# Audio_Output.net
KiCad netlist of a schematic drawn in Altium Designer
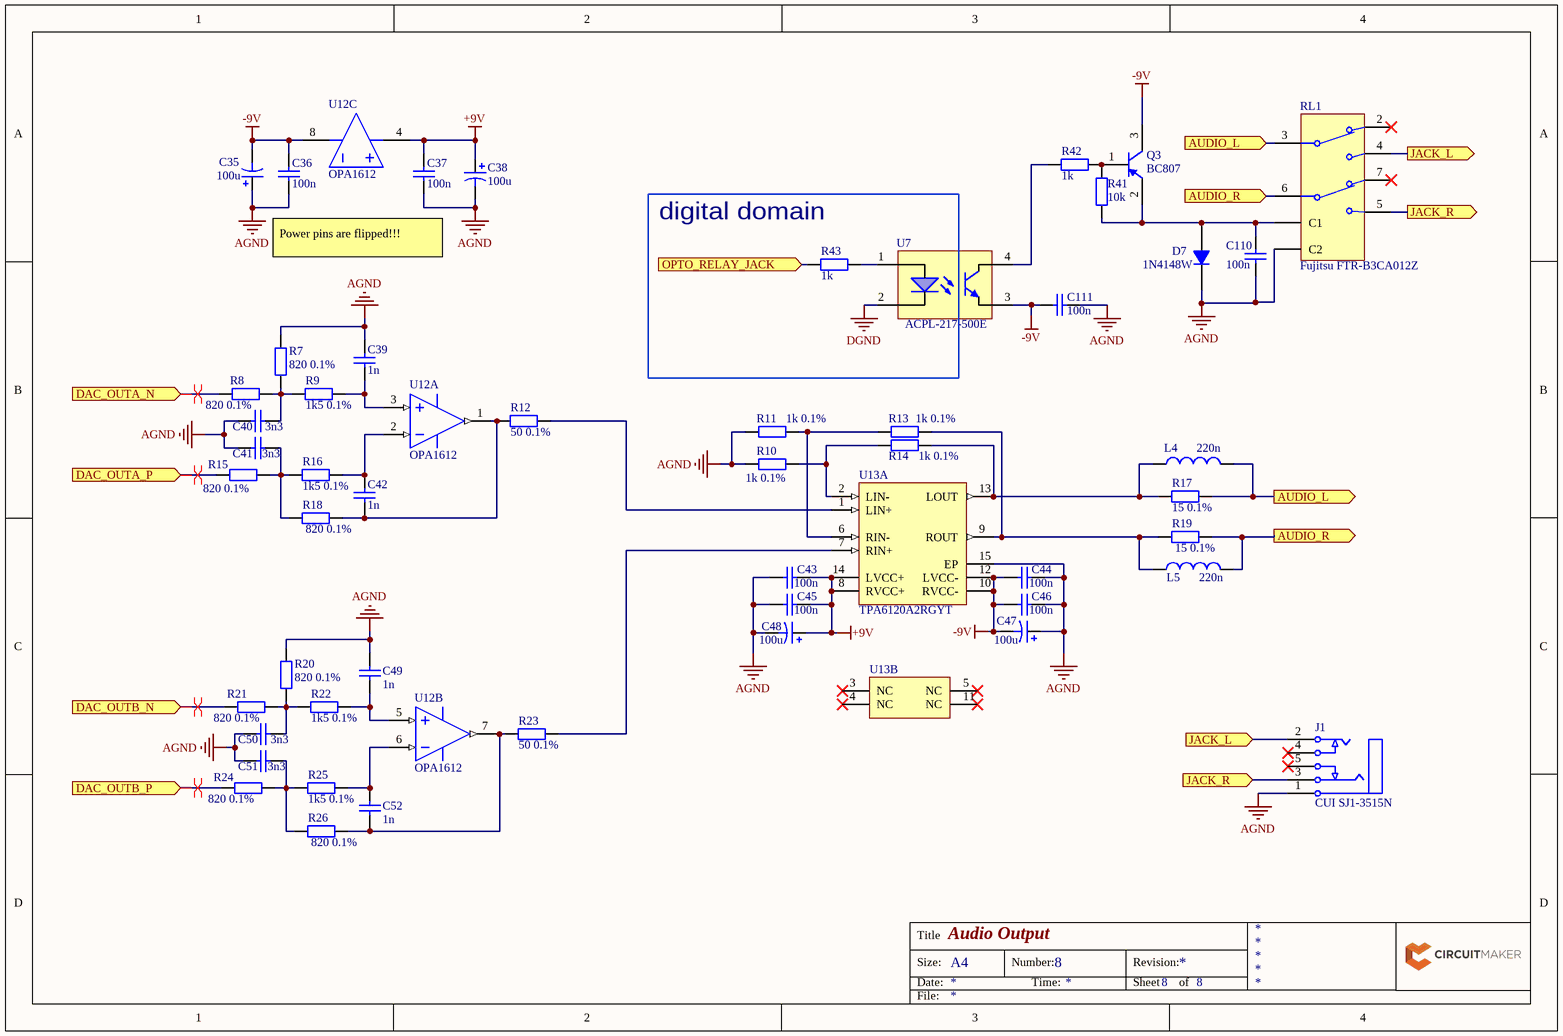
[diagram p0: Audio_Output.SchDoc]

(export (version "E")
  (design (tool "Eeschema 10.0.6"))
  (components
    (comp (ref "C35")
      (value "100u")
      (footprint "PCB-9bfrndi9huxo1n7cihpl-1")
      (description "In a Pack of 25, KEMET 100?F Electrolytic Capacitor 10V dc Through Hole - A758EK107M1AAAE016")
      (fields (field (name "MANUFACTURER PART NUMBER") "A758EK107M1AAAE016"))
      (libsource (lib "FavoritesLibrary") (part "SYM-6546a831a81eba81-3"))
    )
    (comp (ref "C36")
      (value "100n")
      (footprint "PCB-rf0pzaa82dpbeu9l4sxm-1")
      (description "Generic Capacitor 0603")
      (fields (field (name "LCSC PART #") "C14663") (field (name "LCSC PART #_1") "C19702"))
      (libsource (lib "FavoritesLibrary") (part "SYM-x8hddryxw4o380xfi98v-1"))
    )
    (comp (ref "C37")
      (value "100n")
      (footprint "PCB-rf0pzaa82dpbeu9l4sxm-1")
      (description "Generic Capacitor 0603")
      (fields (field (name "LCSC PART #") "C14663") (field (name "LCSC PART #_1") "C19702"))
      (libsource (lib "FavoritesLibrary") (part "SYM-x8hddryxw4o380xfi98v-1"))
    )
    (comp (ref "C38")
      (value "100u")
      (footprint "PCB-9bfrndi9huxo1n7cihpl-1")
      (description "In a Pack of 25, KEMET 100?F Electrolytic Capacitor 10V dc Through Hole - A758EK107M1AAAE016")
      (fields (field (name "MANUFACTURER PART NUMBER") "A758EK107M1AAAE016"))
      (libsource (lib "FavoritesLibrary") (part "SYM-6546a831a81eba81-3"))
    )
    (comp (ref "C39")
      (value "1n")
      (footprint "PCB-rf0pzaa82dpbeu9l4sxm-1")
      (description "Generic Capacitor 0603")
      (libsource (lib "FavoritesLibrary") (part "SYM-x8hddryxw4o380xfi98v-1"))
    )
    (comp (ref "C40")
      (value "3n3")
      (footprint "PCB-rf0pzaa82dpbeu9l4sxm-1")
      (description "Generic Capacitor 0603")
      (libsource (lib "FavoritesLibrary") (part "SYM-x8hddryxw4o380xfi98v-1"))
    )
    (comp (ref "C41")
      (value "3n3")
      (footprint "PCB-rf0pzaa82dpbeu9l4sxm-1")
      (description "Generic Capacitor 0603")
      (libsource (lib "FavoritesLibrary") (part "SYM-x8hddryxw4o380xfi98v-1"))
    )
    (comp (ref "C42")
      (value "1n")
      (footprint "PCB-rf0pzaa82dpbeu9l4sxm-1")
      (description "Generic Capacitor 0603")
      (libsource (lib "FavoritesLibrary") (part "SYM-x8hddryxw4o380xfi98v-1"))
    )
    (comp (ref "C43")
      (value "100n")
      (footprint "PCB-rf0pzaa82dpbeu9l4sxm-1")
      (description "Generic Capacitor 0603")
      (fields (field (name "LCSC PART #") "C14663") (field (name "LCSC PART #_1") "C19702"))
      (libsource (lib "FavoritesLibrary") (part "SYM-x8hddryxw4o380xfi98v-1"))
    )
    (comp (ref "C44")
      (value "100n")
      (footprint "PCB-rf0pzaa82dpbeu9l4sxm-1")
      (description "Generic Capacitor 0603")
      (fields (field (name "LCSC PART #") "C14663") (field (name "LCSC PART #_1") "C19702"))
      (libsource (lib "FavoritesLibrary") (part "SYM-x8hddryxw4o380xfi98v-1"))
    )
    (comp (ref "C45")
      (value "100n")
      (footprint "PCB-rf0pzaa82dpbeu9l4sxm-1")
      (description "Generic Capacitor 0603")
      (fields (field (name "LCSC PART #") "C14663") (field (name "LCSC PART #_1") "C19702"))
      (libsource (lib "FavoritesLibrary") (part "SYM-x8hddryxw4o380xfi98v-1"))
    )
    (comp (ref "C46")
      (value "100n")
      (footprint "PCB-rf0pzaa82dpbeu9l4sxm-1")
      (description "Generic Capacitor 0603")
      (fields (field (name "LCSC PART #") "C14663") (field (name "LCSC PART #_1") "C19702"))
      (libsource (lib "FavoritesLibrary") (part "SYM-x8hddryxw4o380xfi98v-1"))
    )
    (comp (ref "C47")
      (value "100u")
      (footprint "PCB-9bfrndi9huxo1n7cihpl-1")
      (description "In a Pack of 25, KEMET 100?F Electrolytic Capacitor 10V dc Through Hole - A758EK107M1AAAE016")
      (fields (field (name "MANUFACTURER PART NUMBER") "A758EK107M1AAAE016"))
      (libsource (lib "FavoritesLibrary") (part "SYM-6546a831a81eba81-3"))
    )
    (comp (ref "C48")
      (value "100u")
      (footprint "PCB-9bfrndi9huxo1n7cihpl-1")
      (description "In a Pack of 25, KEMET 100?F Electrolytic Capacitor 10V dc Through Hole - A758EK107M1AAAE016")
      (fields (field (name "MANUFACTURER PART NUMBER") "A758EK107M1AAAE016"))
      (libsource (lib "FavoritesLibrary") (part "SYM-6546a831a81eba81-3"))
    )
    (comp (ref "C49")
      (value "1n")
      (footprint "PCB-rf0pzaa82dpbeu9l4sxm-1")
      (description "Generic Capacitor 0603")
      (libsource (lib "FavoritesLibrary") (part "SYM-x8hddryxw4o380xfi98v-1"))
    )
    (comp (ref "C50")
      (value "3n3")
      (footprint "PCB-rf0pzaa82dpbeu9l4sxm-1")
      (description "Generic Capacitor 0603")
      (libsource (lib "FavoritesLibrary") (part "SYM-x8hddryxw4o380xfi98v-1"))
    )
    (comp (ref "C51")
      (value "3n3")
      (footprint "PCB-rf0pzaa82dpbeu9l4sxm-1")
      (description "Generic Capacitor 0603")
      (libsource (lib "FavoritesLibrary") (part "SYM-x8hddryxw4o380xfi98v-1"))
    )
    (comp (ref "C52")
      (value "1n")
      (footprint "PCB-rf0pzaa82dpbeu9l4sxm-1")
      (description "Generic Capacitor 0603")
      (libsource (lib "FavoritesLibrary") (part "SYM-x8hddryxw4o380xfi98v-1"))
    )
    (comp (ref "C110")
      (value "100n")
      (footprint "PCB-rf0pzaa82dpbeu9l4sxm-1")
      (description "Generic Capacitor 0603")
      (fields (field (name "LCSC PART #") "C14663") (field (name "LCSC PART #_1") "C19702"))
      (libsource (lib "FavoritesLibrary") (part "SYM-x8hddryxw4o380xfi98v-1"))
    )
    (comp (ref "C111")
      (value "100n")
      (footprint "PCB-rf0pzaa82dpbeu9l4sxm-1")
      (description "Generic Capacitor 0603")
      (fields (field (name "LCSC PART #") "C14663") (field (name "LCSC PART #_1") "C19702"))
      (libsource (lib "FavoritesLibrary") (part "SYM-x8hddryxw4o380xfi98v-1"))
    )
    (comp (ref "D7")
      (value "1N4148W")
      (footprint "PCB-dk2zqfkr0dm389ntik9k-1")
      (description "Small Signal Diode, Single, 100 V, 300 Ma, 1.25 V, 4 Ns, 2 A Rohs Compliant: Yes")
      (fields (field (name "LCSC PART #") "C81598") (field (name "LCSC PART #_1") "C1546"))
      (libsource (lib "CommunityVault") (part "SYM-791fb3587d52a6d8-9"))
    )
    (comp (ref "J1")
      (value "CUI SJ1-3515N")
      (footprint "PCB-j9vj6bmn4rccphvinwcn-1")
      (description "3.5 mm Right-Angle Stereo Jack, 5 Pin PCB Mount, Non-Threaded")
      (fields (field (name "MANUFACTURER PART NUMBER") "SJ1-3515N"))
      (libsource (lib "FavoritesLibrary") (part "SYM-62caabc32dc3bd0d-1"))
    )
    (comp (ref "L4")
      (value "220n")
      (footprint "PCB-0z5abqka5wqo6pkabrtd-1")
      (description "RF inductor, air core, 2% tol, SMT, RoHS, halogen-free")
      (fields (field (name "MANUFACTURER PART NUMBER") "2222SQ-221GEB"))
      (libsource (lib "FavoritesLibrary") (part "SYM-2243ea3eb191fd84-1"))
    )
    (comp (ref "L5")
      (value "220n")
      (footprint "PCB-0z5abqka5wqo6pkabrtd-1")
      (description "RF inductor, air core, 2% tol, SMT, RoHS, halogen-free")
      (fields (field (name "MANUFACTURER PART NUMBER") "2222SQ-221GEB"))
      (libsource (lib "FavoritesLibrary") (part "SYM-2243ea3eb191fd84-1"))
    )
    (comp (ref "Q3")
      (value "BC807")
      (footprint "ONSC-SOT-23-3-318-08_V")
      (description "General Purpose Transistor, PNP Silicon, 3-Pin SOT-23, Pb-Free, Tape and Reel")
      (fields (field (name "MANUFACTURER PART NUMBER") "BC807-16LT1G"))
      (libsource (lib "CommunityVault") (part "CMP-857821-2"))
    )
    (comp (ref "R7")
      (value "820 0.1%")
      (footprint "PCB-3d5y3t7f8drf35yjcj59-1")
      (description "Resistor 0603")
      (libsource (lib "") (part "SYM-xcu3s4ikiffkkgbeyow5-1_3"))
    )
    (comp (ref "R8")
      (value "820 0.1%")
      (footprint "PCB-3d5y3t7f8drf35yjcj59-1")
      (description "Resistor 0603")
      (libsource (lib "") (part "SYM-xcu3s4ikiffkkgbeyow5-1_1"))
    )
    (comp (ref "R9")
      (value "1k5 0.1%")
      (footprint "PCB-3d5y3t7f8drf35yjcj59-1")
      (description "Resistor 0603")
      (libsource (lib "") (part "SYM-xcu3s4ikiffkkgbeyow5-1_2"))
    )
    (comp (ref "R10")
      (value "1k 0.1%")
      (footprint "PCB-3d5y3t7f8drf35yjcj59-1")
      (description "Resistor 0603")
      (libsource (lib "") (part "SYM-xcu3s4ikiffkkgbeyow5-1_1"))
    )
    (comp (ref "R11")
      (value "1k 0.1%")
      (footprint "PCB-3d5y3t7f8drf35yjcj59-1")
      (description "Resistor 0603")
      (libsource (lib "") (part "SYM-xcu3s4ikiffkkgbeyow5-1_1"))
    )
    (comp (ref "R12")
      (value "50 0.1%")
      (footprint "PCB-3d5y3t7f8drf35yjcj59-1")
      (description "Resistor 0603")
      (libsource (lib "") (part "SYM-xcu3s4ikiffkkgbeyow5-1_2"))
    )
    (comp (ref "R13")
      (value "1k 0.1%")
      (footprint "PCB-3d5y3t7f8drf35yjcj59-1")
      (description "Resistor 0603")
      (libsource (lib "") (part "SYM-xcu3s4ikiffkkgbeyow5-1_1"))
    )
    (comp (ref "R14")
      (value "1k 0.1%")
      (footprint "PCB-3d5y3t7f8drf35yjcj59-1")
      (description "Resistor 0603")
      (libsource (lib "") (part "SYM-xcu3s4ikiffkkgbeyow5-1_1"))
    )
    (comp (ref "R15")
      (value "820 0.1%")
      (footprint "PCB-3d5y3t7f8drf35yjcj59-1")
      (description "Resistor 0603")
      (libsource (lib "") (part "SYM-xcu3s4ikiffkkgbeyow5-1_1"))
    )
    (comp (ref "R16")
      (value "1k5 0.1%")
      (footprint "PCB-3d5y3t7f8drf35yjcj59-1")
      (description "Resistor 0603")
      (libsource (lib "") (part "SYM-xcu3s4ikiffkkgbeyow5-1_2"))
    )
    (comp (ref "R17")
      (value "15 0.1%")
      (footprint "PCB-3d5y3t7f8drf35yjcj59-1")
      (description "Resistor 0603")
      (libsource (lib "") (part "SYM-xcu3s4ikiffkkgbeyow5-1_2"))
    )
    (comp (ref "R18")
      (value "820 0.1%")
      (footprint "PCB-3d5y3t7f8drf35yjcj59-1")
      (description "Resistor 0603")
      (libsource (lib "") (part "SYM-xcu3s4ikiffkkgbeyow5-1_1"))
    )
    (comp (ref "R19")
      (value "15 0.1%")
      (footprint "PCB-3d5y3t7f8drf35yjcj59-1")
      (description "Resistor 0603")
      (libsource (lib "") (part "SYM-xcu3s4ikiffkkgbeyow5-1_2"))
    )
    (comp (ref "R20")
      (value "820 0.1%")
      (footprint "PCB-3d5y3t7f8drf35yjcj59-1")
      (description "Resistor 0603")
      (libsource (lib "") (part "SYM-xcu3s4ikiffkkgbeyow5-1_3"))
    )
    (comp (ref "R21")
      (value "820 0.1%")
      (footprint "PCB-3d5y3t7f8drf35yjcj59-1")
      (description "Resistor 0603")
      (libsource (lib "") (part "SYM-xcu3s4ikiffkkgbeyow5-1_1"))
    )
    (comp (ref "R22")
      (value "1k5 0.1%")
      (footprint "PCB-3d5y3t7f8drf35yjcj59-1")
      (description "Resistor 0603")
      (libsource (lib "") (part "SYM-xcu3s4ikiffkkgbeyow5-1_2"))
    )
    (comp (ref "R23")
      (value "50 0.1%")
      (footprint "PCB-3d5y3t7f8drf35yjcj59-1")
      (description "Resistor 0603")
      (libsource (lib "") (part "SYM-xcu3s4ikiffkkgbeyow5-1_2"))
    )
    (comp (ref "R24")
      (value "820 0.1%")
      (footprint "PCB-3d5y3t7f8drf35yjcj59-1")
      (description "Resistor 0603")
      (libsource (lib "") (part "SYM-xcu3s4ikiffkkgbeyow5-1_1"))
    )
    (comp (ref "R25")
      (value "1k5 0.1%")
      (footprint "PCB-3d5y3t7f8drf35yjcj59-1")
      (description "Resistor 0603")
      (libsource (lib "") (part "SYM-xcu3s4ikiffkkgbeyow5-1_2"))
    )
    (comp (ref "R26")
      (value "820 0.1%")
      (footprint "PCB-3d5y3t7f8drf35yjcj59-1")
      (description "Resistor 0603")
      (libsource (lib "") (part "SYM-xcu3s4ikiffkkgbeyow5-1_1"))
    )
    (comp (ref "R41")
      (value "10k")
      (footprint "PCB-3d5y3t7f8drf35yjcj59-1")
      (description "Resistor 0603")
      (fields (field (name "LCSC PART #") "C25804") (field (name "LCSC PART #_1") "C21190"))
      (libsource (lib "FavoritesLibrary") (part "SYM-xcu3s4ikiffkkgbeyow5-1"))
    )
    (comp (ref "R42")
      (value "1k")
      (footprint "PCB-3d5y3t7f8drf35yjcj59-1")
      (description "Resistor 0603")
      (fields (field (name "LCSC PART #") "C21190"))
      (libsource (lib "") (part "SYM-xcu3s4ikiffkkgbeyow5-1_1"))
    )
    (comp (ref "R43")
      (value "1k")
      (footprint "PCB-3d5y3t7f8drf35yjcj59-1")
      (description "Resistor 0603")
      (fields (field (name "LCSC PART #") "C21190"))
      (libsource (lib "") (part "SYM-xcu3s4ikiffkkgbeyow5-1_1"))
    )
    (comp (ref "RL1")
      (value "Fujitsu FTR-B3CA012Z")
      (footprint "PCB-79j3gj3ralb8es1cyg77-1")
      (description "Miniature Relay 2A, coil voltage 12V DC, 2 changeover contact (2C), 1A/30V DC, 0.3A/125VAC")
      (fields (field (name "MANUFACTURER PART NUMBER") "FTR-B3CA012Z"))
      (libsource (lib "FavoritesLibrary") (part "SYM-2945e043254ff682-1"))
    )
    (comp (ref "U7")
      (value "ACPL-217-500E")
      (footprint "PCB-tryrgihdrozpg2dv6q87-1")
      (description "Optocoupler; SMD; Channels: 1; Out: transistor; 3kV; SO4")
      (libsource (lib "FavoritesLibrary") (part "SYM-b8a973267dee676e-1"))
    )
    (comp (ref "U12")
      (value "OPA1612")
      (footprint "TI-D8_M")
      (fields (field (name "MANUFACTURER PART NUMBER") "OPA1612AIDR"))
      (libsource (lib "CommunityVault") (part "CMP-1335515-4"))
    )
    (comp (ref "U13")
      (value "TPA6120A2RGYT")
      (footprint "RGY14-2050X2050TP")
      (description "HEADPHONE AMP, CLASS AB, VQFN-14")
      (fields (field (name "MANUFACTURER PART NUMBER") "TPA6120A2RGYT"))
      (libsource (lib "FavoritesLibrary") (part "TI-TPA6120A2DWP20-3730X2350TP"))
    )
  )
  (nets
    (net (code "1") (name "+9V") (class "Default")
      (node (ref "C37") (pin "1") (pinfunction "1_1") (pintype "passive"))
      (node (ref "C38") (pin "1") (pinfunction "1_1") (pintype "passive"))
      (node (ref "C43") (pin "2") (pinfunction "2_2") (pintype "passive"))
      (node (ref "C45") (pin "2") (pinfunction "2_2") (pintype "passive"))
      (node (ref "C48") (pin "1") (pinfunction "1_1") (pintype "passive"))
      (node (ref "U12") (pin "4") (pinfunction "V-_4") (pintype "power_in"))
      (node (ref "U13") (pin "14") (pinfunction "LVCC+_14") (pintype "power_in"))
      (node (ref "U13") (pin "8") (pinfunction "RVCC+_8") (pintype "power_in"))
    )
    (net (code "2") (name "-9V") (class "Default")
      (node (ref "C111") (pin "1") (pinfunction "1_1") (pintype "passive"))
      (node (ref "C35") (pin "2") (pinfunction "2_2") (pintype "passive"))
      (node (ref "C36") (pin "1") (pinfunction "1_1") (pintype "passive"))
      (node (ref "C44") (pin "1") (pinfunction "1_1") (pintype "passive"))
      (node (ref "C46") (pin "1") (pinfunction "1_1") (pintype "passive"))
      (node (ref "C47") (pin "2") (pinfunction "2_2") (pintype "passive"))
      (node (ref "Q3") (pin "3") (pinfunction "C_3") (pintype "passive"))
      (node (ref "U12") (pin "8") (pinfunction "V+_8") (pintype "power_in"))
      (node (ref "U13") (pin "10") (pinfunction "RVCC-_10") (pintype "power_in"))
      (node (ref "U13") (pin "12") (pinfunction "LVCC-_12") (pintype "power_in"))
      (node (ref "U7") (pin "3") (pintype "passive"))
    )
    (net (code "3") (name "/AUDIO_L") (class "Default")
      (node (ref "L4") (pin "2") (pinfunction "2_2") (pintype "passive"))
      (node (ref "R17") (pin "2") (pinfunction "2_2") (pintype "passive"))
      (node (ref "RL1") (pin "3") (pinfunction "3_3") (pintype "passive"))
    )
    (net (code "4") (name "/AUDIO_R") (class "Default")
      (node (ref "L5") (pin "2") (pinfunction "2_2") (pintype "passive"))
      (node (ref "R19") (pin "2") (pinfunction "2_2") (pintype "passive"))
      (node (ref "RL1") (pin "6") (pinfunction "6_6") (pintype "passive"))
    )
    (net (code "5") (name "/DAC_OUTA_N") (class "Default")
      (node (ref "R8") (pin "2") (pinfunction "2_2") (pintype "passive"))
    )
    (net (code "6") (name "/DAC_OUTA_P") (class "Default")
      (node (ref "R15") (pin "2") (pinfunction "2_2") (pintype "passive"))
    )
    (net (code "7") (name "/DAC_OUTB_N") (class "Default")
      (node (ref "R21") (pin "2") (pinfunction "2_2") (pintype "passive"))
    )
    (net (code "8") (name "/DAC_OUTB_P") (class "Default")
      (node (ref "R24") (pin "2") (pinfunction "2_2") (pintype "passive"))
    )
    (net (code "9") (name "/JACK_L") (class "Default")
      (node (ref "J1") (pin "2") (pinfunction "TIP_2") (pintype "passive"))
      (node (ref "RL1") (pin "4") (pinfunction "4_4") (pintype "passive"))
    )
    (net (code "10") (name "/JACK_R") (class "Default")
      (node (ref "J1") (pin "3") (pinfunction "RING_3") (pintype "passive"))
      (node (ref "RL1") (pin "5") (pinfunction "5_5") (pintype "passive"))
    )
    (net (code "11") (name "/OPTO_RELAY_JACK") (class "Default")
      (node (ref "R43") (pin "2") (pinfunction "2_2") (pintype "passive"))
    )
    (net (code "12") (name "AGND") (class "Default")
      (node (ref "C110") (pin "1") (pinfunction "1_1") (pintype "passive"))
      (node (ref "C111") (pin "2") (pinfunction "2_2") (pintype "passive"))
      (node (ref "C35") (pin "1") (pinfunction "1_1") (pintype "passive"))
      (node (ref "C36") (pin "2") (pinfunction "2_2") (pintype "passive"))
      (node (ref "C37") (pin "2") (pinfunction "2_2") (pintype "passive"))
      (node (ref "C38") (pin "2") (pinfunction "2_2") (pintype "passive"))
      (node (ref "C39") (pin "1") (pinfunction "1_1") (pintype "passive"))
      (node (ref "C40") (pin "1") (pinfunction "1_1") (pintype "passive"))
      (node (ref "C41") (pin "1") (pinfunction "1_1") (pintype "passive"))
      (node (ref "C43") (pin "1") (pinfunction "1_1") (pintype "passive"))
      (node (ref "C44") (pin "2") (pinfunction "2_2") (pintype "passive"))
      (node (ref "C45") (pin "1") (pinfunction "1_1") (pintype "passive"))
      (node (ref "C46") (pin "2") (pinfunction "2_2") (pintype "passive"))
      (node (ref "C47") (pin "1") (pinfunction "1_1") (pintype "passive"))
      (node (ref "C48") (pin "2") (pinfunction "2_2") (pintype "passive"))
      (node (ref "C49") (pin "2") (pinfunction "2_2") (pintype "passive"))
      (node (ref "C50") (pin "2") (pinfunction "2_2") (pintype "passive"))
      (node (ref "C51") (pin "1") (pinfunction "1_1") (pintype "passive"))
      (node (ref "D7") (pin "2") (pinfunction "K_2") (pintype "passive"))
      (node (ref "J1") (pin "1") (pinfunction "SLEEVE_1") (pintype "passive"))
      (node (ref "R10") (pin "2") (pinfunction "2_2") (pintype "passive"))
      (node (ref "R11") (pin "2") (pinfunction "2_2") (pintype "passive"))
      (node (ref "R20") (pin "2") (pinfunction "2_2") (pintype "passive"))
      (node (ref "R7") (pin "2") (pinfunction "2_2") (pintype "passive"))
      (node (ref "RL1") (pin "8") (pinfunction "C2_8") (pintype "passive"))
      (node (ref "U13") (pin "15") (pinfunction "EP_15") (pintype "power_in"))
    )
    (net (code "13") (name "DGND") (class "Default") (node (ref "U7") (pin "2") (pintype "passive")))
    (net (code "14") (name "Net-(C40-Pad2)") (class "Default")
      (node (ref "C40") (pin "2") (pinfunction "2_2") (pintype "passive"))
      (node (ref "R7") (pin "1") (pinfunction "1_1") (pintype "passive"))
      (node (ref "R8") (pin "1") (pinfunction "1_1") (pintype "passive"))
      (node (ref "R9") (pin "1") (pinfunction "1_1") (pintype "passive"))
    )
    (net (code "15") (name "Net-(C41-Pad2)") (class "Default")
      (node (ref "C41") (pin "2") (pinfunction "2_2") (pintype "passive"))
      (node (ref "R15") (pin "1") (pinfunction "1_1") (pintype "passive"))
      (node (ref "R16") (pin "1") (pinfunction "1_1") (pintype "passive"))
      (node (ref "R18") (pin "2") (pinfunction "2_2") (pintype "passive"))
    )
    (net (code "16") (name "Net-(C50-Pad1)") (class "Default")
      (node (ref "C50") (pin "1") (pinfunction "1_1") (pintype "passive"))
      (node (ref "R20") (pin "1") (pinfunction "1_1") (pintype "passive"))
      (node (ref "R21") (pin "1") (pinfunction "1_1") (pintype "passive"))
      (node (ref "R22") (pin "1") (pinfunction "1_1") (pintype "passive"))
    )
    (net (code "17") (name "Net-(C51-Pad2)") (class "Default")
      (node (ref "C51") (pin "2") (pinfunction "2_2") (pintype "passive"))
      (node (ref "R24") (pin "1") (pinfunction "1_1") (pintype "passive"))
      (node (ref "R25") (pin "1") (pinfunction "1_1") (pintype "passive"))
      (node (ref "R26") (pin "2") (pinfunction "2_2") (pintype "passive"))
    )
    (net (code "18") (name "Net-(D7-A)") (class "Default")
      (node (ref "C110") (pin "2") (pinfunction "2_2") (pintype "passive"))
      (node (ref "D7") (pin "1") (pinfunction "A_1") (pintype "passive"))
      (node (ref "Q3") (pin "2") (pinfunction "E_2") (pintype "passive"))
      (node (ref "R41") (pin "2") (pinfunction "2_2") (pintype "passive"))
      (node (ref "RL1") (pin "1") (pinfunction "C1_1") (pintype "passive"))
    )
    (net (code "19") (name "Net-(Q3-B)") (class "Default")
      (node (ref "Q3") (pin "1") (pinfunction "B_1") (pintype "passive"))
      (node (ref "R41") (pin "1") (pinfunction "1_1") (pintype "passive"))
      (node (ref "R42") (pin "1") (pinfunction "1_1") (pintype "passive"))
    )
    (net (code "20") (name "Net-(R42-Pad2)") (class "Default")
      (node (ref "R42") (pin "2") (pinfunction "2_2") (pintype "passive"))
      (node (ref "U7") (pin "4") (pintype "passive"))
    )
    (net (code "21") (name "Net-(U7-A)") (class "Default")
      (node (ref "R43") (pin "1") (pinfunction "1_1") (pintype "passive"))
      (node (ref "U7") (pin "1") (pinfunction "A_1") (pintype "passive"))
    )
    (net (code "22") (name "Net-(U12A-IN_A+)") (class "Default")
      (node (ref "C39") (pin "2") (pinfunction "2_2") (pintype "passive"))
      (node (ref "R9") (pin "2") (pinfunction "2_2") (pintype "passive"))
      (node (ref "U12") (pin "3") (pinfunction "IN_A+_3") (pintype "input"))
    )
    (net (code "23") (name "Net-(U12A-IN_A-)") (class "Default")
      (node (ref "C42") (pin "1") (pinfunction "1_1") (pintype "passive"))
      (node (ref "R16") (pin "2") (pinfunction "2_2") (pintype "passive"))
      (node (ref "U12") (pin "2") (pinfunction "IN_A-_2") (pintype "input"))
    )
    (net (code "24") (name "Net-(U12A-OUT_A)") (class "Default")
      (node (ref "C42") (pin "2") (pinfunction "2_2") (pintype "passive"))
      (node (ref "R12") (pin "1") (pinfunction "1_1") (pintype "passive"))
      (node (ref "R18") (pin "1") (pinfunction "1_1") (pintype "passive"))
      (node (ref "U12") (pin "1") (pinfunction "OUT_A_1") (pintype "output"))
    )
    (net (code "25") (name "Net-(U12B-IN_B+)") (class "Default")
      (node (ref "C49") (pin "1") (pinfunction "1_1") (pintype "passive"))
      (node (ref "R22") (pin "2") (pinfunction "2_2") (pintype "passive"))
      (node (ref "U12") (pin "5") (pinfunction "IN_B+_5") (pintype "input"))
    )
    (net (code "26") (name "Net-(U12B-IN_B-)") (class "Default")
      (node (ref "C52") (pin "2") (pinfunction "2_2") (pintype "passive"))
      (node (ref "R25") (pin "2") (pinfunction "2_2") (pintype "passive"))
      (node (ref "U12") (pin "6") (pinfunction "IN_B-_6") (pintype "input"))
    )
    (net (code "27") (name "Net-(U12B-OUT_B)") (class "Default")
      (node (ref "C52") (pin "1") (pinfunction "1_1") (pintype "passive"))
      (node (ref "R23") (pin "1") (pinfunction "1_1") (pintype "passive"))
      (node (ref "R26") (pin "1") (pinfunction "1_1") (pintype "passive"))
      (node (ref "U12") (pin "7") (pinfunction "OUT_B_7") (pintype "output"))
    )
    (net (code "28") (name "Net-(U13A-LIN+)") (class "Default")
      (node (ref "R12") (pin "2") (pinfunction "2_2") (pintype "passive"))
      (node (ref "U13") (pin "1") (pinfunction "LIN+_1") (pintype "input"))
    )
    (net (code "29") (name "Net-(U13A-LIN-)") (class "Default")
      (node (ref "R10") (pin "1") (pinfunction "1_1") (pintype "passive"))
      (node (ref "R14") (pin "2") (pinfunction "2_2") (pintype "passive"))
      (node (ref "U13") (pin "2") (pinfunction "LIN-_2") (pintype "input"))
    )
    (net (code "30") (name "Net-(U13A-LOUT)") (class "Default")
      (node (ref "L4") (pin "1") (pinfunction "1_1") (pintype "passive"))
      (node (ref "R14") (pin "1") (pinfunction "1_1") (pintype "passive"))
      (node (ref "R17") (pin "1") (pinfunction "1_1") (pintype "passive"))
      (node (ref "U13") (pin "13") (pinfunction "LOUT_13") (pintype "output"))
    )
    (net (code "31") (name "Net-(U13A-RIN+)") (class "Default")
      (node (ref "R23") (pin "2") (pinfunction "2_2") (pintype "passive"))
      (node (ref "U13") (pin "7") (pinfunction "RIN+_7") (pintype "input"))
    )
    (net (code "32") (name "Net-(U13A-RIN-)") (class "Default")
      (node (ref "R11") (pin "1") (pinfunction "1_1") (pintype "passive"))
      (node (ref "R13") (pin "2") (pinfunction "2_2") (pintype "passive"))
      (node (ref "U13") (pin "6") (pinfunction "RIN-_6") (pintype "input"))
    )
    (net (code "33") (name "Net-(U13A-ROUT)") (class "Default")
      (node (ref "L5") (pin "1") (pinfunction "1_1") (pintype "passive"))
      (node (ref "R13") (pin "1") (pinfunction "1_1") (pintype "passive"))
      (node (ref "R19") (pin "1") (pinfunction "1_1") (pintype "passive"))
      (node (ref "U13") (pin "9") (pinfunction "ROUT_9") (pintype "output"))
    )
    (net (code "34") (name "unconnected-(J1-Pad4)") (class "Default")
      (node (ref "J1") (pin "4") (pintype "power_in+no_connect"))
    )
    (net (code "35") (name "unconnected-(J1-Pad5)") (class "Default")
      (node (ref "J1") (pin "5") (pintype "power_in+no_connect"))
    )
    (net (code "36") (name "unconnected-(RL1-Pad2)") (class "Default")
      (node (ref "RL1") (pin "2") (pinfunction "2_2") (pintype "passive+no_connect"))
    )
    (net (code "37") (name "unconnected-(RL1-Pad7)") (class "Default")
      (node (ref "RL1") (pin "7") (pinfunction "7_7") (pintype "passive+no_connect"))
    )
    (net (code "38") (name "unconnected-(U13B-NC-Pad3)") (class "Default")
      (node (ref "U13") (pin "3") (pinfunction "NC_3") (pintype "passive+no_connect"))
    )
    (net (code "39") (name "unconnected-(U13B-NC-Pad4)") (class "Default")
      (node (ref "U13") (pin "4") (pinfunction "NC_4") (pintype "passive+no_connect"))
    )
    (net (code "40") (name "unconnected-(U13B-NC-Pad5)") (class "Default")
      (node (ref "U13") (pin "5") (pinfunction "NC_5") (pintype "passive+no_connect"))
    )
    (net (code "41") (name "unconnected-(U13B-NC-Pad11)") (class "Default")
      (node (ref "U13") (pin "11") (pinfunction "NC_11") (pintype "passive+no_connect"))
    )
  )
)
